# core.net
KiCad netlist of a schematic drawn in EAGLE
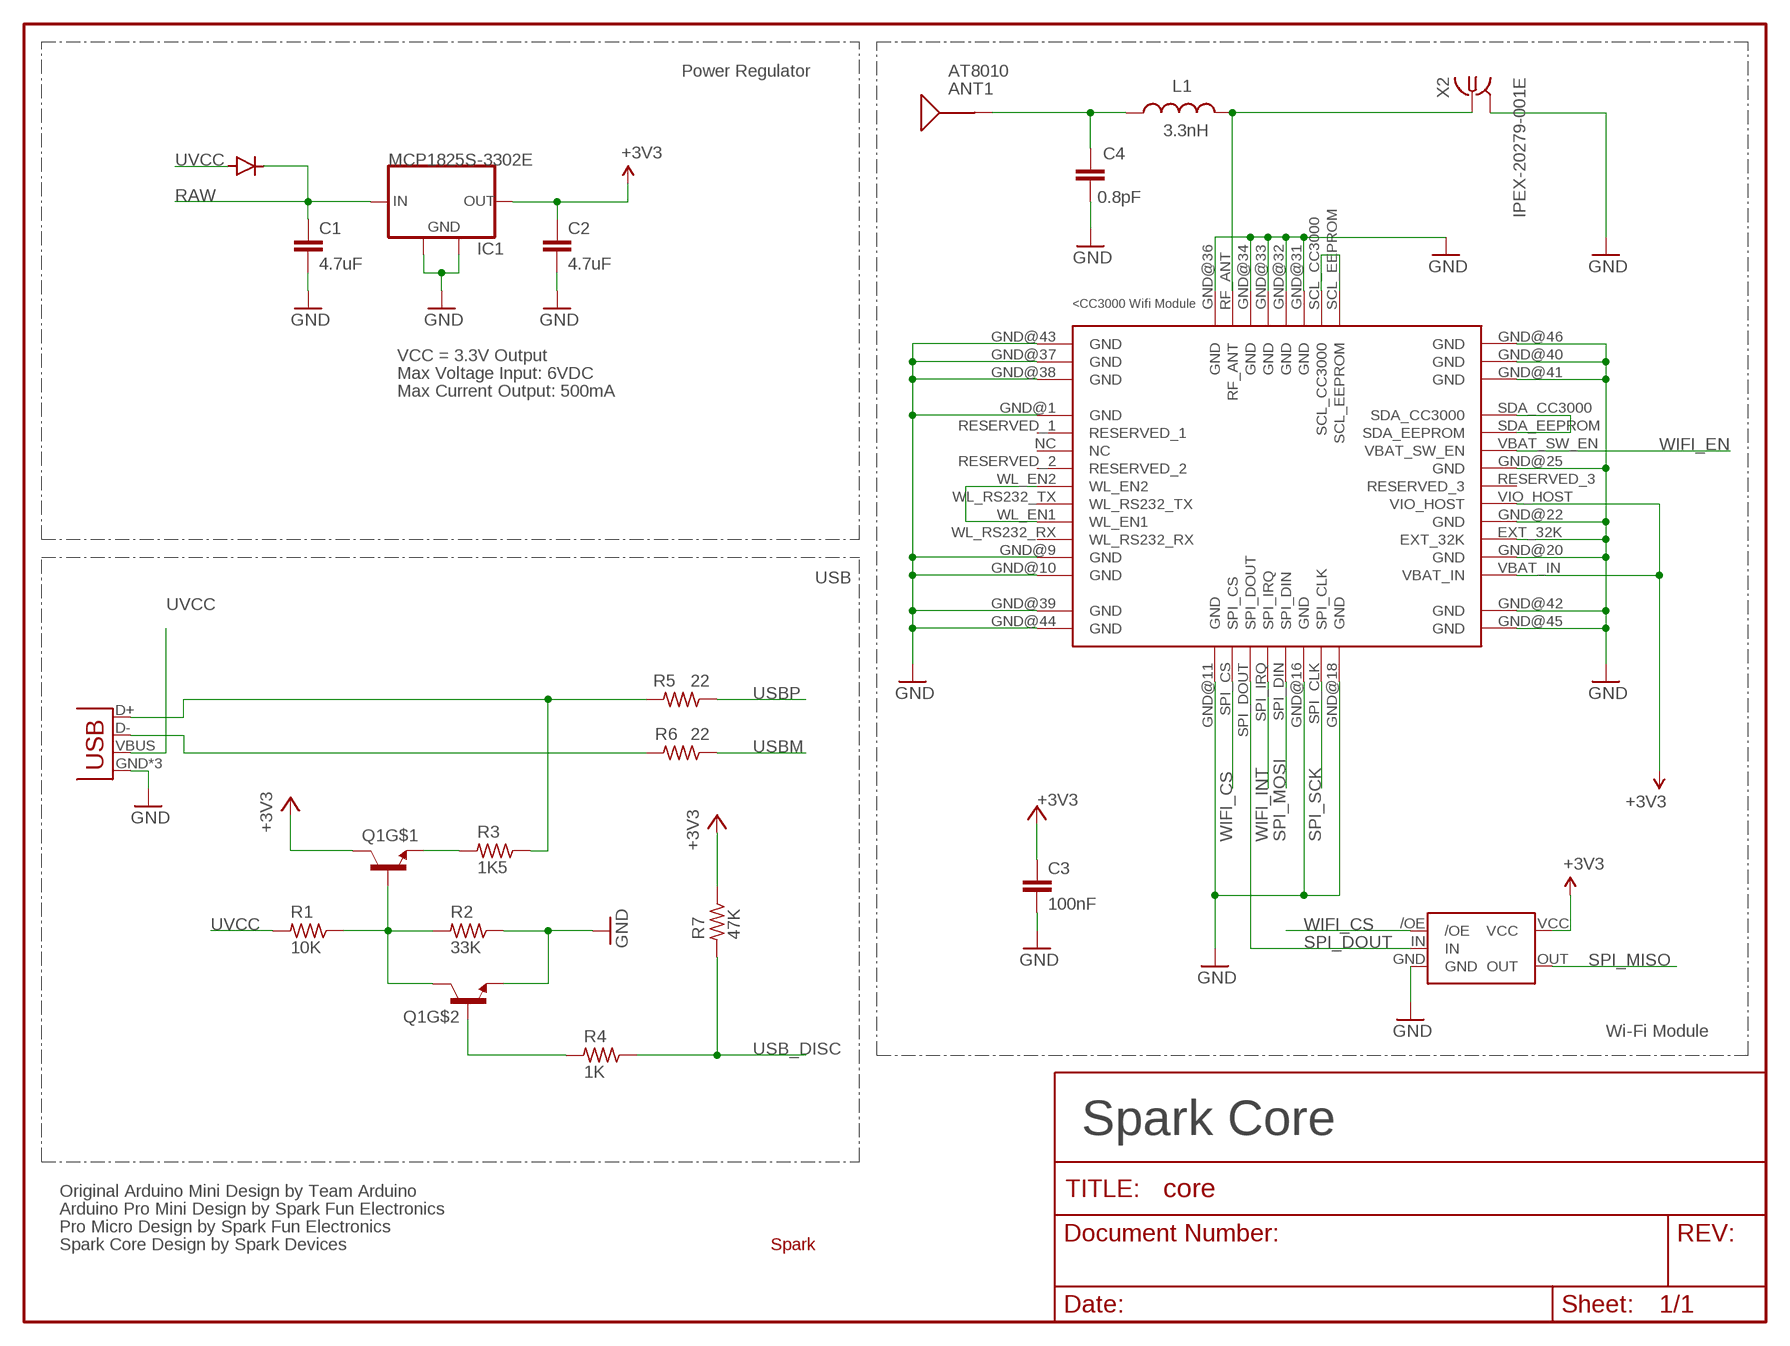
[diagram p0: schematic, sheet 1, part 1 of 2]
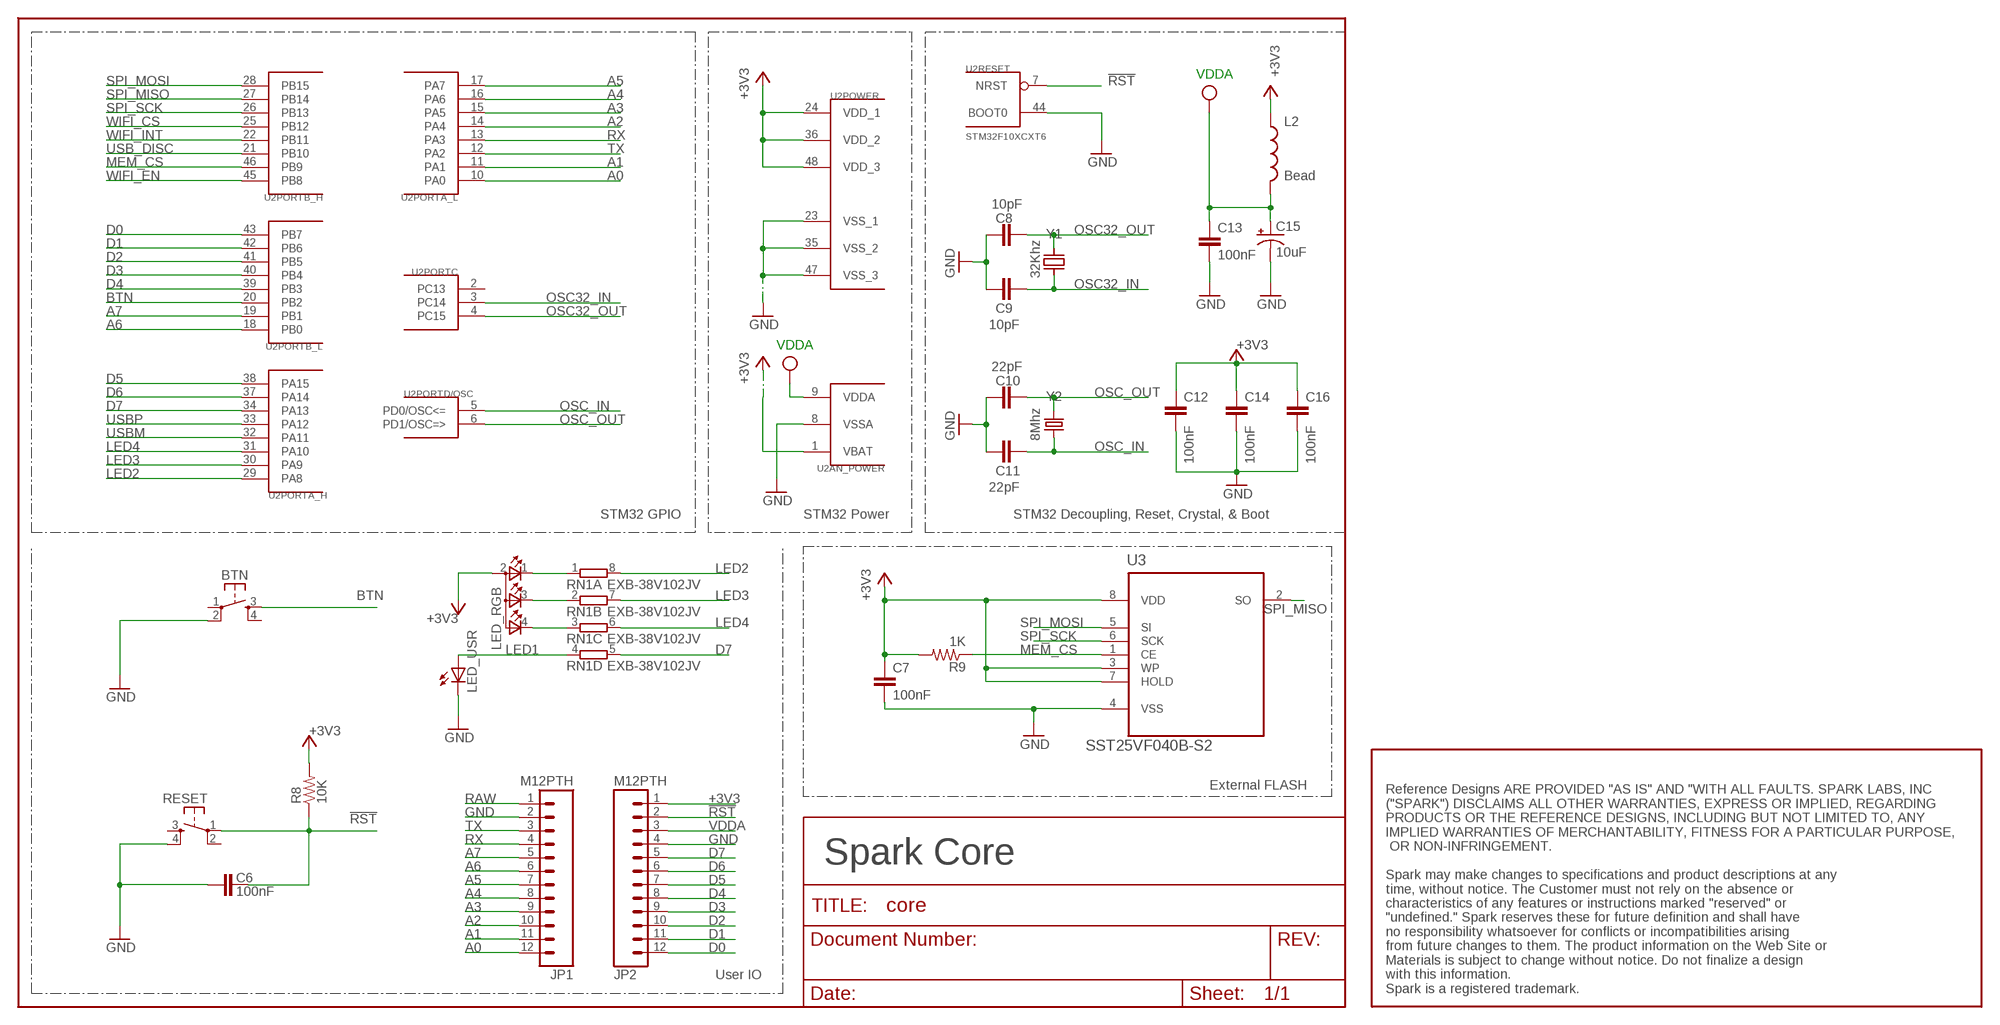
[diagram p1: schematic, sheet 1, part 2 of 2]

(export (version "E")
  (design (tool "Eeschema 10.0.6"))
  (components
    (comp (ref "ANT1")
      (value "AT8010")
      (footprint "eagle-import:AT8010")
      (libsource (lib "eagle-import") (part "AT8010"))
    )
    (comp (ref "BTN")
      (value "KMR211GLFS")
      (footprint "eagle-import:TACTILE_SWITCH_SMD")
      (libsource (lib "eagle-import") (part "TAC_SWITCHSMD"))
    )
    (comp (ref "C1")
      (value "4.7uF")
      (footprint "eagle-import:C0603")
      (libsource (lib "eagle-import") (part "C-EUC0603"))
    )
    (comp (ref "C2")
      (value "4.7uF")
      (footprint "eagle-import:C0603")
      (libsource (lib "eagle-import") (part "C-EUC0603"))
    )
    (comp (ref "C3")
      (value "100nF")
      (footprint "eagle-import:C0603")
      (libsource (lib "eagle-import") (part "C-EUC0603"))
    )
    (comp (ref "C4")
      (value "0.8pF")
      (footprint "eagle-import:C0603")
      (libsource (lib "eagle-import") (part "C-EUC0603"))
    )
    (comp (ref "C6")
      (value "100nF")
      (footprint "eagle-import:C0603")
      (libsource (lib "eagle-import") (part "C-EUC0603"))
    )
    (comp (ref "C7")
      (value "100nF")
      (footprint "eagle-import:C0603")
      (libsource (lib "eagle-import") (part "C-EUC0603"))
    )
    (comp (ref "C8")
      (value "10pF")
      (footprint "eagle-import:C0603")
      (libsource (lib "eagle-import") (part "C-EUC0603"))
    )
    (comp (ref "C9")
      (value "10pF")
      (footprint "eagle-import:C0603")
      (libsource (lib "eagle-import") (part "C-EUC0603"))
    )
    (comp (ref "C10")
      (value "22pF")
      (footprint "eagle-import:C0603")
      (libsource (lib "eagle-import") (part "C-EUC0603"))
    )
    (comp (ref "C11")
      (value "22pF")
      (footprint "eagle-import:C0603")
      (libsource (lib "eagle-import") (part "C-EUC0603"))
    )
    (comp (ref "C12")
      (value "100nF")
      (footprint "eagle-import:C0603")
      (libsource (lib "eagle-import") (part "C-EUC0603"))
    )
    (comp (ref "C13")
      (value "100nF")
      (footprint "eagle-import:C0603")
      (libsource (lib "eagle-import") (part "C-EUC0603"))
    )
    (comp (ref "C14")
      (value "100nF")
      (footprint "eagle-import:C0603")
      (libsource (lib "eagle-import") (part "C-EUC0603"))
    )
    (comp (ref "C15")
      (value "10uF")
      (footprint "eagle-import:EIA3216")
      (libsource (lib "eagle-import") (part "TANT-CAP1206"))
    )
    (comp (ref "C16")
      (value "100nF")
      (footprint "eagle-import:C0603")
      (libsource (lib "eagle-import") (part "C-EUC0603"))
    )
    (comp (ref "D1")
      (value "DIODE")
      (footprint "eagle-import:DIODE-DO-220AA(SMP)")
      (libsource (lib "eagle-import") (part "DIODE"))
    )
    (comp (ref "IC1")
      (value "MCP1825S-3302E")
      (footprint "eagle-import:SOT223")
      (libsource (lib "eagle-import") (part "MCP1825S-SOT223"))
    )
    (comp (ref "JP1")
      (value "M12PTH")
      (footprint "eagle-import:1X12-SMALL-PADS")
      (libsource (lib "eagle-import") (part "M12PTH"))
    )
    (comp (ref "JP2")
      (value "M12PTH")
      (footprint "eagle-import:1X12-SMALL-PADS")
      (libsource (lib "eagle-import") (part "M12PTH"))
    )
    (comp (ref "L1")
      (value "3.3nH")
      (footprint "eagle-import:0603")
      (libsource (lib "eagle-import") (part "INDUCTOR0603"))
    )
    (comp (ref "L2")
      (value "Bead")
      (footprint "eagle-import:0603")
      (libsource (lib "eagle-import") (part "INDUCTOR0603"))
    )
    (comp (ref "LED_RGB")
      (value "TOPLED-3PLCC")
      (footprint "eagle-import:P-LCC-4-3")
      (libsource (lib "eagle-import") (part "TOPLED-3PLCC"))
    )
    (comp (ref "LED_USR")
      (value "LED0603")
      (footprint "eagle-import:LED-0603")
      (libsource (lib "eagle-import") (part "LED0603"))
    )
    (comp (ref "Q1")
      (value "MMDT3904")
      (footprint "eagle-import:SOT363")
      (libsource (lib "eagle-import") (part "MMDT3904"))
    )
    (comp (ref "R1")
      (value "10K")
      (footprint "eagle-import:R0603")
      (libsource (lib "eagle-import") (part "R-US_R0603"))
    )
    (comp (ref "R2")
      (value "33K")
      (footprint "eagle-import:R0603")
      (libsource (lib "eagle-import") (part "R-US_R0603"))
    )
    (comp (ref "R3")
      (value "1K5")
      (footprint "eagle-import:R0603")
      (libsource (lib "eagle-import") (part "R-US_R0603"))
    )
    (comp (ref "R4")
      (value "1K")
      (footprint "eagle-import:R0603")
      (libsource (lib "eagle-import") (part "R-US_R0603"))
    )
    (comp (ref "R5")
      (value "22")
      (footprint "eagle-import:R0603")
      (libsource (lib "eagle-import") (part "R-US_R0603"))
    )
    (comp (ref "R6")
      (value "22")
      (footprint "eagle-import:R0603")
      (libsource (lib "eagle-import") (part "R-US_R0603"))
    )
    (comp (ref "R7")
      (value "47K")
      (footprint "eagle-import:R0603")
      (libsource (lib "eagle-import") (part "R-US_R0603"))
    )
    (comp (ref "R8")
      (value "10K")
      (footprint "eagle-import:R0603")
      (libsource (lib "eagle-import") (part "R-US_R0603"))
    )
    (comp (ref "R9")
      (value "1K")
      (footprint "eagle-import:R0603")
      (libsource (lib "eagle-import") (part "R-US_R0603"))
    )
    (comp (ref "RESET")
      (value "KMR211GLFS")
      (footprint "eagle-import:TACTILE_SWITCH_SMD")
      (libsource (lib "eagle-import") (part "TAC_SWITCHSMD"))
    )
    (comp (ref "RN1")
      (value "EXB-38V102JV")
      (footprint "eagle-import:EXB38V")
      (libsource (lib "eagle-import") (part "4R-NEXB38V"))
    )
    (comp (ref "U$1")
      (value "SPARK_LOGO2")
      (footprint "eagle-import:SPARK_LOGO2")
      (libsource (lib "eagle-import") (part "SPARK_LOGO2"))
    )
    (comp (ref "U1")
      (value "CC3000")
      (footprint "eagle-import:CC3000")
      (libsource (lib "eagle-import") (part "CC3000"))
    )
    (comp (ref "U2")
      (value "STM32F10XCXT6")
      (footprint "eagle-import:TQFP48")
      (libsource (lib "eagle-import") (part "STM32F10XCXT6"))
    )
    (comp (ref "U3")
      (value "SST25VF040B-S2")
      (footprint "eagle-import:SOIC127P790X216-8N")
      (libsource (lib "eagle-import") (part "SST25VF040B-S2"))
    )
    (comp (ref "U4")
      (value "NL17SZ125SOT553")
      (footprint "eagle-import:SOT-553")
      (libsource (lib "eagle-import") (part "NL17SZ125SOT553"))
    )
    (comp (ref "X1")
      (value "USB-MICROB")
      (footprint "eagle-import:USB-MICROB-SLOT-HOLE")
      (libsource (lib "eagle-import") (part "USBUSB-MICROB-SLOT-HOLE"))
    )
    (comp (ref "X2")
      (value "IPEX-20279-001E")
      (footprint "eagle-import:IPEX-20279-001E")
      (libsource (lib "eagle-import") (part "IPEX-20279-001E"))
    )
    (comp (ref "Y1")
      (value "32Khz")
      (footprint "eagle-import:FC135")
      (libsource (lib "eagle-import") (part "Q_FC135"))
    )
    (comp (ref "Y2")
      (value "8Mhz")
      (footprint "eagle-import:CRYSTAL-SMD-5X3")
      (libsource (lib "eagle-import") (part "CRYSTAL5X3"))
    )
  )
  (nets
    (net (code "1") (name "+3V3") (class "Default")
      (node (ref "C12") (pin "1") (pinfunction "1_1") (pintype "passive"))
      (node (ref "C14") (pin "1") (pinfunction "1_1") (pintype "passive"))
      (node (ref "C16") (pin "1") (pinfunction "1_1") (pintype "passive"))
      (node (ref "C2") (pin "1") (pinfunction "1_1") (pintype "passive"))
      (node (ref "C3") (pin "1") (pinfunction "1_1") (pintype "passive"))
      (node (ref "C7") (pin "1") (pinfunction "1_1") (pintype "passive"))
      (node (ref "IC1") (pin "3") (pinfunction "OUT_3") (pintype "output"))
      (node (ref "JP2") (pin "1") (pinfunction "1_1") (pintype "passive"))
      (node (ref "L2") (pin "1") (pinfunction "1_1") (pintype "passive"))
      (node (ref "LED_RGB") (pin "2") (pinfunction "A2_2") (pintype "passive"))
      (node (ref "Q1") (pin "3") (pinfunction "C_3") (pintype "passive"))
      (node (ref "R7") (pin "1") (pinfunction "1_1") (pintype "passive"))
      (node (ref "R8") (pin "2") (pinfunction "2_2") (pintype "passive"))
      (node (ref "R9") (pin "2") (pinfunction "2_2") (pintype "passive"))
      (node (ref "U1") (pin "VBAT_IN") (pinfunction "VBAT_IN_VBAT_IN") (pintype "power_in"))
      (node (ref "U1") (pin "VIO_HOST") (pinfunction "VIO_HOST_VIO_HOST") (pintype "power_in"))
      (node (ref "U2") (pin "1") (pinfunction "VBAT_1") (pintype "power_in"))
      (node (ref "U2") (pin "24") (pinfunction "VDD_1_24") (pintype "power_in"))
      (node (ref "U2") (pin "36") (pinfunction "VDD_2_36") (pintype "power_in"))
      (node (ref "U2") (pin "48") (pinfunction "VDD_3_48") (pintype "power_in"))
      (node (ref "U3") (pin "3") (pinfunction "WP_3") (pintype "input"))
      (node (ref "U3") (pin "7") (pinfunction "HOLD_7") (pintype "input"))
      (node (ref "U3") (pin "8") (pinfunction "VDD_8") (pintype "power_in"))
      (node (ref "U4") (pin "VCC") (pinfunction "VCC_VCC") (pintype "bidirectional"))
    )
    (net (code "2") (name "/A0") (class "Default")
      (node (ref "JP1") (pin "12") (pinfunction "12_12") (pintype "passive"))
      (node (ref "U2") (pin "10") (pinfunction "PA0_10") (pintype "bidirectional"))
    )
    (net (code "3") (name "/A1") (class "Default")
      (node (ref "JP1") (pin "11") (pinfunction "11_11") (pintype "passive"))
      (node (ref "U2") (pin "11") (pinfunction "PA1_11") (pintype "bidirectional"))
    )
    (net (code "4") (name "/A2") (class "Default")
      (node (ref "JP1") (pin "10") (pinfunction "10_10") (pintype "passive"))
      (node (ref "U2") (pin "14") (pinfunction "PA4_14") (pintype "bidirectional"))
    )
    (net (code "5") (name "/A3") (class "Default")
      (node (ref "JP1") (pin "9") (pinfunction "9_9") (pintype "passive"))
      (node (ref "U2") (pin "15") (pinfunction "PA5_15") (pintype "bidirectional"))
    )
    (net (code "6") (name "/A4") (class "Default")
      (node (ref "JP1") (pin "8") (pinfunction "8_8") (pintype "passive"))
      (node (ref "U2") (pin "16") (pinfunction "PA6_16") (pintype "bidirectional"))
    )
    (net (code "7") (name "/A5") (class "Default")
      (node (ref "JP1") (pin "7") (pinfunction "7_7") (pintype "passive"))
      (node (ref "U2") (pin "17") (pinfunction "PA7_17") (pintype "bidirectional"))
    )
    (net (code "8") (name "/A6") (class "Default")
      (node (ref "JP1") (pin "6") (pinfunction "6_6") (pintype "passive"))
      (node (ref "U2") (pin "18") (pinfunction "PB0_18") (pintype "bidirectional"))
    )
    (net (code "9") (name "/A7") (class "Default")
      (node (ref "JP1") (pin "5") (pinfunction "5_5") (pintype "passive"))
      (node (ref "U2") (pin "19") (pinfunction "PB1_19") (pintype "bidirectional"))
    )
    (net (code "10") (name "/BTN") (class "Default")
      (node (ref "BTN") (pin "3") (pinfunction "3_3") (pintype "passive"))
      (node (ref "U2") (pin "20") (pinfunction "PB2_20") (pintype "bidirectional"))
    )
    (net (code "11") (name "/D0") (class "Default")
      (node (ref "JP2") (pin "12") (pinfunction "12_12") (pintype "passive"))
      (node (ref "U2") (pin "43") (pinfunction "PB7_43") (pintype "bidirectional"))
    )
    (net (code "12") (name "/D1") (class "Default")
      (node (ref "JP2") (pin "11") (pinfunction "11_11") (pintype "passive"))
      (node (ref "U2") (pin "42") (pinfunction "PB6_42") (pintype "bidirectional"))
    )
    (net (code "13") (name "/D2") (class "Default")
      (node (ref "JP2") (pin "10") (pinfunction "10_10") (pintype "passive"))
      (node (ref "U2") (pin "41") (pinfunction "PB5_41") (pintype "bidirectional"))
    )
    (net (code "14") (name "/D3") (class "Default")
      (node (ref "JP2") (pin "9") (pinfunction "9_9") (pintype "passive"))
      (node (ref "U2") (pin "40") (pinfunction "PB4_40") (pintype "bidirectional"))
    )
    (net (code "15") (name "/D4") (class "Default")
      (node (ref "JP2") (pin "8") (pinfunction "8_8") (pintype "passive"))
      (node (ref "U2") (pin "39") (pinfunction "PB3_39") (pintype "bidirectional"))
    )
    (net (code "16") (name "/D5") (class "Default")
      (node (ref "JP2") (pin "7") (pinfunction "7_7") (pintype "passive"))
      (node (ref "U2") (pin "38") (pinfunction "PA15_38") (pintype "bidirectional"))
    )
    (net (code "17") (name "/D6") (class "Default")
      (node (ref "JP2") (pin "6") (pinfunction "6_6") (pintype "passive"))
      (node (ref "U2") (pin "37") (pinfunction "PA14_37") (pintype "bidirectional"))
    )
    (net (code "18") (name "/D7") (class "Default")
      (node (ref "JP2") (pin "5") (pinfunction "5_5") (pintype "passive"))
      (node (ref "RN1") (pin "5") (pinfunction "2_5") (pintype "passive"))
      (node (ref "U2") (pin "34") (pinfunction "PA13_34") (pintype "bidirectional"))
    )
    (net (code "19") (name "/LED1") (class "Default")
      (node (ref "LED_USR") (pin "A") (pinfunction "A_A") (pintype "passive"))
      (node (ref "RN1") (pin "4") (pinfunction "1_4") (pintype "passive"))
    )
    (net (code "20") (name "/LED2") (class "Default")
      (node (ref "RN1") (pin "8") (pinfunction "2_8") (pintype "passive"))
      (node (ref "U2") (pin "29") (pinfunction "PA8_29") (pintype "bidirectional"))
    )
    (net (code "21") (name "/LED3") (class "Default")
      (node (ref "RN1") (pin "7") (pinfunction "2_7") (pintype "passive"))
      (node (ref "U2") (pin "30") (pinfunction "PA9_30") (pintype "bidirectional"))
    )
    (net (code "22") (name "/LED4") (class "Default")
      (node (ref "RN1") (pin "6") (pinfunction "2_6") (pintype "passive"))
      (node (ref "U2") (pin "31") (pinfunction "PA10_31") (pintype "bidirectional"))
    )
    (net (code "23") (name "/MEM_CS") (class "Default")
      (node (ref "R9") (pin "1") (pinfunction "1_1") (pintype "passive"))
      (node (ref "U2") (pin "46") (pinfunction "PB9_46") (pintype "bidirectional"))
      (node (ref "U3") (pin "1") (pinfunction "CE_1") (pintype "input"))
    )
    (net (code "24") (name "/OSC32_IN") (class "Default")
      (node (ref "C9") (pin "1") (pinfunction "1_1") (pintype "passive"))
      (node (ref "U2") (pin "3") (pinfunction "PC14_3") (pintype "bidirectional"))
      (node (ref "Y1") (pin "X1") (pinfunction "1_X1") (pintype "passive"))
    )
    (net (code "25") (name "/OSC32_OUT") (class "Default")
      (node (ref "C8") (pin "1") (pinfunction "1_1") (pintype "passive"))
      (node (ref "U2") (pin "4") (pinfunction "PC15_4") (pintype "bidirectional"))
      (node (ref "Y1") (pin "X2") (pinfunction "2_X2") (pintype "passive"))
    )
    (net (code "26") (name "/OSC_IN") (class "Default")
      (node (ref "C11") (pin "1") (pinfunction "1_1") (pintype "passive"))
      (node (ref "U2") (pin "5") (pinfunction "PD0/OSC<=_5") (pintype "bidirectional"))
      (node (ref "Y2") (pin "1") (pinfunction "1_1") (pintype "passive"))
    )
    (net (code "27") (name "/OSC_OUT") (class "Default")
      (node (ref "C10") (pin "1") (pinfunction "1_1") (pintype "passive"))
      (node (ref "U2") (pin "6") (pinfunction "PD1/OSC=>_6") (pintype "bidirectional"))
      (node (ref "Y2") (pin "3") (pinfunction "2_3") (pintype "passive"))
    )
    (net (code "28") (name "/RAW") (class "Default")
      (node (ref "C1") (pin "1") (pinfunction "1_1") (pintype "passive"))
      (node (ref "D1") (pin "CATHODE") (pinfunction "CATHODE_CATHODE") (pintype "bidirectional"))
      (node (ref "IC1") (pin "1") (pinfunction "IN_1") (pintype "input"))
      (node (ref "JP1") (pin "1") (pinfunction "1_1") (pintype "passive"))
    )
    (net (code "29") (name "/RX") (class "Default")
      (node (ref "JP1") (pin "4") (pinfunction "4_4") (pintype "passive"))
      (node (ref "U2") (pin "13") (pinfunction "PA3_13") (pintype "bidirectional"))
    )
    (net (code "30") (name "/SPI_DOUT") (class "Default")
      (node (ref "U1") (pin "SPI_DOUT") (pinfunction "SPI_DOUT_SPI_DOUT") (pintype "output"))
      (node (ref "U4") (pin "IN") (pinfunction "IN_IN") (pintype "bidirectional"))
    )
    (net (code "31") (name "/SPI_MISO") (class "Default")
      (node (ref "U2") (pin "27") (pinfunction "PB14_27") (pintype "bidirectional"))
      (node (ref "U3") (pin "2") (pinfunction "SO_2") (pintype "output"))
      (node (ref "U4") (pin "OUT") (pinfunction "OUT_OUT") (pintype "bidirectional"))
    )
    (net (code "32") (name "/SPI_MOSI") (class "Default")
      (node (ref "U1") (pin "SPI_DIN") (pinfunction "SPI_DIN_SPI_DIN") (pintype "input"))
      (node (ref "U2") (pin "28") (pinfunction "PB15_28") (pintype "bidirectional"))
      (node (ref "U3") (pin "5") (pinfunction "SI_5") (pintype "input"))
    )
    (net (code "33") (name "/SPI_SCK") (class "Default")
      (node (ref "U1") (pin "SPI_CLK") (pinfunction "SPI_CLK_SPI_CLK") (pintype "input"))
      (node (ref "U2") (pin "26") (pinfunction "PB13_26") (pintype "bidirectional"))
      (node (ref "U3") (pin "6") (pinfunction "SCK_6") (pintype "input"))
    )
    (net (code "34") (name "/TX") (class "Default")
      (node (ref "JP1") (pin "3") (pinfunction "3_3") (pintype "passive"))
      (node (ref "U2") (pin "12") (pinfunction "PA2_12") (pintype "bidirectional"))
    )
    (net (code "35") (name "/USBM") (class "Default")
      (node (ref "R6") (pin "1") (pinfunction "1_1") (pintype "passive"))
      (node (ref "U2") (pin "32") (pinfunction "PA11_32") (pintype "bidirectional"))
    )
    (net (code "36") (name "/USBP") (class "Default")
      (node (ref "R5") (pin "1") (pinfunction "1_1") (pintype "passive"))
      (node (ref "U2") (pin "33") (pinfunction "PA12_33") (pintype "bidirectional"))
    )
    (net (code "37") (name "/USB_DISC") (class "Default")
      (node (ref "R4") (pin "1") (pinfunction "1_1") (pintype "passive"))
      (node (ref "R7") (pin "2") (pinfunction "2_2") (pintype "passive"))
      (node (ref "U2") (pin "21") (pinfunction "PB10_21") (pintype "bidirectional"))
    )
    (net (code "38") (name "/UVCC") (class "Default")
      (node (ref "D1") (pin "ANODE") (pinfunction "ANODE_ANODE") (pintype "bidirectional"))
      (node (ref "R1") (pin "2") (pinfunction "2_2") (pintype "passive"))
      (node (ref "X1") (pin "VBUS") (pinfunction "VBUS_VBUS") (pintype "bidirectional"))
    )
    (net (code "39") (name "/WIFI_CS") (class "Default")
      (node (ref "U1") (pin "SPI_CS") (pinfunction "SPI_CS_SPI_CS") (pintype "input"))
      (node (ref "U2") (pin "25") (pinfunction "PB12_25") (pintype "bidirectional"))
      (node (ref "U4") (pin "/OE") (pinfunction "/OE_/OE") (pintype "bidirectional"))
    )
    (net (code "40") (name "/WIFI_EN") (class "Default")
      (node (ref "U1") (pin "VBAT_SW_EN") (pinfunction "VBAT_SW_EN_VBAT_SW_EN") (pintype "input"))
      (node (ref "U2") (pin "45") (pinfunction "PB8_45") (pintype "bidirectional"))
    )
    (net (code "41") (name "/WIFI_INT") (class "Default")
      (node (ref "U1") (pin "SPI_IRQ") (pinfunction "SPI_IRQ_SPI_IRQ") (pintype "output"))
      (node (ref "U2") (pin "22") (pinfunction "PB11_22") (pintype "bidirectional"))
    )
    (net (code "42") (name "/~{RST}") (class "Default")
      (node (ref "C6") (pin "2") (pinfunction "2_2") (pintype "passive"))
      (node (ref "JP2") (pin "2") (pinfunction "2_2") (pintype "passive"))
      (node (ref "R8") (pin "1") (pinfunction "1_1") (pintype "passive"))
      (node (ref "RESET") (pin "1") (pinfunction "1_1") (pintype "passive"))
      (node (ref "U2") (pin "7") (pinfunction "NRST_7") (pintype "input"))
    )
    (net (code "43") (name "GND") (class "Default")
      (node (ref "BTN") (pin "2") (pinfunction "2_2") (pintype "passive"))
      (node (ref "C1") (pin "2") (pinfunction "2_2") (pintype "passive"))
      (node (ref "C10") (pin "2") (pinfunction "2_2") (pintype "passive"))
      (node (ref "C11") (pin "2") (pinfunction "2_2") (pintype "passive"))
      (node (ref "C12") (pin "2") (pinfunction "2_2") (pintype "passive"))
      (node (ref "C13") (pin "2") (pinfunction "2_2") (pintype "passive"))
      (node (ref "C14") (pin "2") (pinfunction "2_2") (pintype "passive"))
      (node (ref "C15") (pin "C") (pinfunction "-_C") (pintype "passive"))
      (node (ref "C16") (pin "2") (pinfunction "2_2") (pintype "passive"))
      (node (ref "C2") (pin "2") (pinfunction "2_2") (pintype "passive"))
      (node (ref "C3") (pin "2") (pinfunction "2_2") (pintype "passive"))
      (node (ref "C4") (pin "2") (pinfunction "2_2") (pintype "passive"))
      (node (ref "C6") (pin "1") (pinfunction "1_1") (pintype "passive"))
      (node (ref "C7") (pin "2") (pinfunction "2_2") (pintype "passive"))
      (node (ref "C8") (pin "2") (pinfunction "2_2") (pintype "passive"))
      (node (ref "C9") (pin "2") (pinfunction "2_2") (pintype "passive"))
      (node (ref "IC1") (pin "2") (pinfunction "GND_2") (pintype "power_in"))
      (node (ref "IC1") (pin "4") (pinfunction "GND_4") (pintype "power_in"))
      (node (ref "JP1") (pin "2") (pinfunction "2_2") (pintype "passive"))
      (node (ref "JP2") (pin "4") (pinfunction "4_4") (pintype "passive"))
      (node (ref "LED_USR") (pin "C") (pinfunction "C_C") (pintype "passive"))
      (node (ref "Q1") (pin "1") (pinfunction "E_1") (pintype "passive"))
      (node (ref "R2") (pin "1") (pinfunction "1_1") (pintype "passive"))
      (node (ref "RESET") (pin "4") (pinfunction "4_4") (pintype "passive"))
      (node (ref "U1") (pin "EXT_32K") (pinfunction "EXT_32K_EXT_32K") (pintype "bidirectional"))
      (node (ref "U1") (pin "GND@1") (pinfunction "GND_GND@1") (pintype "power_in"))
      (node (ref "U1") (pin "GND@10") (pinfunction "GND_GND@10") (pintype "power_in"))
      (node (ref "U1") (pin "GND@11") (pinfunction "GND_GND@11") (pintype "power_in"))
      (node (ref "U1") (pin "GND@16") (pinfunction "GND_GND@16") (pintype "power_in"))
      (node (ref "U1") (pin "GND@18") (pinfunction "GND_GND@18") (pintype "power_in"))
      (node (ref "U1") (pin "GND@20") (pinfunction "GND_GND@20") (pintype "power_in"))
      (node (ref "U1") (pin "GND@22") (pinfunction "GND_GND@22") (pintype "power_in"))
      (node (ref "U1") (pin "GND@25") (pinfunction "GND_GND@25") (pintype "power_in"))
      (node (ref "U1") (pin "GND@31") (pinfunction "GND_GND@31") (pintype "power_in"))
      (node (ref "U1") (pin "GND@32") (pinfunction "GND_GND@32") (pintype "power_in"))
      (node (ref "U1") (pin "GND@33") (pinfunction "GND_GND@33") (pintype "power_in"))
      (node (ref "U1") (pin "GND@34") (pinfunction "GND_GND@34") (pintype "power_in"))
      (node (ref "U1") (pin "GND@36") (pinfunction "GND_GND@36") (pintype "power_in"))
      (node (ref "U1") (pin "GND@37") (pinfunction "GND_GND@37") (pintype "power_in"))
      (node (ref "U1") (pin "GND@38") (pinfunction "GND_GND@38") (pintype "power_in"))
      (node (ref "U1") (pin "GND@39") (pinfunction "GND_GND@39") (pintype "power_in"))
      (node (ref "U1") (pin "GND@40") (pinfunction "GND_GND@40") (pintype "power_in"))
      (node (ref "U1") (pin "GND@41") (pinfunction "GND_GND@41") (pintype "power_in"))
      (node (ref "U1") (pin "GND@42") (pinfunction "GND_GND@42") (pintype "power_in"))
      (node (ref "U1") (pin "GND@43") (pinfunction "GND_GND@43") (pintype "power_in"))
      (node (ref "U1") (pin "GND@44") (pinfunction "GND_GND@44") (pintype "power_in"))
      (node (ref "U1") (pin "GND@45") (pinfunction "GND_GND@45") (pintype "power_in"))
      (node (ref "U1") (pin "GND@46") (pinfunction "GND_GND@46") (pintype "power_in"))
      (node (ref "U1") (pin "GND@9") (pinfunction "GND_GND@9") (pintype "power_in"))
      (node (ref "U2") (pin "23") (pinfunction "VSS_1_23") (pintype "power_in"))
      (node (ref "U2") (pin "35") (pinfunction "VSS_2_35") (pintype "power_in"))
      (node (ref "U2") (pin "44") (pinfunction "BOOT0_44") (pintype "input"))
      (node (ref "U2") (pin "47") (pinfunction "VSS_3_47") (pintype "power_in"))
      (node (ref "U2") (pin "8") (pinfunction "VSSA_8") (pintype "power_in"))
      (node (ref "U3") (pin "4") (pinfunction "VSS_4") (pintype "passive"))
      (node (ref "U4") (pin "GND") (pinfunction "GND_GND") (pintype "bidirectional"))
      (node (ref "X1") (pin "GND") (pinfunction "GND_GND") (pintype "bidirectional"))
      (node (ref "X1") (pin "MT1") (pinfunction "GND_MT1") (pintype "bidirectional"))
      (node (ref "X1") (pin "MT2") (pinfunction "GND_MT2") (pintype "bidirectional"))
      (node (ref "X2") (pin "2@1") (pinfunction "GND_2@1") (pintype "passive"))
      (node (ref "X2") (pin "2@2") (pinfunction "GND_2@2") (pintype "passive"))
    )
    (net (code "44") (name "Net-(ANT1-SIGNAL)") (class "Default")
      (node (ref "ANT1") (pin "SIG") (pinfunction "SIGNAL_SIG") (pintype "bidirectional"))
      (node (ref "C4") (pin "1") (pinfunction "1_1") (pintype "passive"))
      (node (ref "L1") (pin "1") (pinfunction "1_1") (pintype "passive"))
    )
    (net (code "45") (name "Net-(L1-Pad2)") (class "Default")
      (node (ref "L1") (pin "2") (pinfunction "2_2") (pintype "passive"))
      (node (ref "U1") (pin "RF_ANT") (pinfunction "RF_ANT_RF_ANT") (pintype "bidirectional"))
      (node (ref "X2") (pin "1") (pinfunction "1_1") (pintype "passive"))
    )
    (net (code "46") (name "Net-(LED_RGB-CBLUE)") (class "Default")
      (node (ref "LED_RGB") (pin "3") (pinfunction "CBLUE_3") (pintype "passive"))
      (node (ref "RN1") (pin "2") (pinfunction "1_2") (pintype "passive"))
    )
    (net (code "47") (name "Net-(LED_RGB-CGREEN)") (class "Default")
      (node (ref "LED_RGB") (pin "4") (pinfunction "CGREEN_4") (pintype "passive"))
      (node (ref "RN1") (pin "3") (pinfunction "1_3") (pintype "passive"))
    )
    (net (code "48") (name "Net-(LED_RGB-CRED)") (class "Default")
      (node (ref "LED_RGB") (pin "1") (pinfunction "CRED_1") (pintype "passive"))
      (node (ref "RN1") (pin "1") (pinfunction "1_1") (pintype "passive"))
    )
    (net (code "49") (name "Net-(Q1A-B)") (class "Default")
      (node (ref "Q1") (pin "5") (pinfunction "B_5") (pintype "passive"))
      (node (ref "Q1") (pin "6") (pinfunction "C_6") (pintype "passive"))
      (node (ref "R1") (pin "1") (pinfunction "1_1") (pintype "passive"))
      (node (ref "R2") (pin "2") (pinfunction "2_2") (pintype "passive"))
    )
    (net (code "50") (name "Net-(Q1A-E)") (class "Default")
      (node (ref "Q1") (pin "4") (pinfunction "E_4") (pintype "passive"))
      (node (ref "R3") (pin "2") (pinfunction "2_2") (pintype "passive"))
    )
    (net (code "51") (name "Net-(Q1B-B)") (class "Default")
      (node (ref "Q1") (pin "2") (pinfunction "B_2") (pintype "passive"))
      (node (ref "R4") (pin "2") (pinfunction "2_2") (pintype "passive"))
    )
    (net (code "52") (name "Net-(R3-Pad1)") (class "Default")
      (node (ref "R3") (pin "1") (pinfunction "1_1") (pintype "passive"))
      (node (ref "R5") (pin "2") (pinfunction "2_2") (pintype "passive"))
      (node (ref "X1") (pin "D+") (pinfunction "D+_D+") (pintype "bidirectional"))
    )
    (net (code "53") (name "Net-(R6-Pad2)") (class "Default")
      (node (ref "R6") (pin "2") (pinfunction "2_2") (pintype "passive"))
      (node (ref "X1") (pin "D-") (pinfunction "D-_D-") (pintype "bidirectional"))
    )
    (net (code "54") (name "Net-(U1-PadSCL_CC3000)") (class "Default")
      (node (ref "U1") (pin "SCL_CC3000") (pinfunction "SCL_CC3000_SCL_CC3000") (pintype "bidirectional"))
      (node (ref "U1") (pin "SCL_EEPROM") (pinfunction "SCL_EEPROM_SCL_EEPROM") (pintype "bidirectional"))
    )
    (net (code "55") (name "Net-(U1-PadSDA_CC3000)") (class "Default")
      (node (ref "U1") (pin "SDA_CC3000") (pinfunction "SDA_CC3000_SDA_CC3000") (pintype "bidirectional"))
      (node (ref "U1") (pin "SDA_EEPROM") (pinfunction "SDA_EEPROM_SDA_EEPROM") (pintype "bidirectional"))
    )
    (net (code "56") (name "Net-(U1-PadWL_EN1)") (class "Default")
      (node (ref "U1") (pin "WL_EN1") (pinfunction "WL_EN1_WL_EN1") (pintype "input"))
      (node (ref "U1") (pin "WL_EN2") (pinfunction "WL_EN2_WL_EN2") (pintype "input"))
    )
    (net (code "57") (name "VCC") (class "Default")
      (node (ref "C13") (pin "1") (pinfunction "1_1") (pintype "passive"))
      (node (ref "C15") (pin "A") (pinfunction "+_A") (pintype "passive"))
      (node (ref "JP2") (pin "3") (pinfunction "3_3") (pintype "passive"))
      (node (ref "L2") (pin "2") (pinfunction "2_2") (pintype "passive"))
      (node (ref "U2") (pin "9") (pinfunction "VDDA_9") (pintype "power_in"))
    )
    (net (code "58") (name "unconnected-(BTN-Pad1)") (class "Default")
      (node (ref "BTN") (pin "1") (pinfunction "1_1") (pintype "passive"))
    )
    (net (code "59") (name "unconnected-(BTN-Pad4)") (class "Default")
      (node (ref "BTN") (pin "4") (pinfunction "4_4") (pintype "passive"))
    )
    (net (code "60") (name "unconnected-(RESET-Pad2)") (class "Default")
      (node (ref "RESET") (pin "2") (pinfunction "2_2") (pintype "passive"))
    )
    (net (code "61") (name "unconnected-(RESET-Pad3)") (class "Default")
      (node (ref "RESET") (pin "3") (pinfunction "3_3") (pintype "passive"))
    )
    (net (code "62") (name "unconnected-(U1-PadNC)") (class "Default")
      (node (ref "U1") (pin "NC") (pinfunction "NC_NC") (pintype "no_connect"))
    )
    (net (code "63") (name "unconnected-(U1-PadRESERVED_1)") (class "Default")
      (node (ref "U1") (pin "RESERVED_1") (pinfunction "RESERVED_1_RESERVED_1") (pintype "bidirectional"))
    )
    (net (code "64") (name "unconnected-(U1-PadRESERVED_2)") (class "Default")
      (node (ref "U1") (pin "RESERVED_2") (pinfunction "RESERVED_2_RESERVED_2") (pintype "bidirectional"))
    )
    (net (code "65") (name "unconnected-(U1-PadRESERVED_3)") (class "Default")
      (node (ref "U1") (pin "RESERVED_3") (pinfunction "RESERVED_3_RESERVED_3") (pintype "bidirectional"))
    )
    (net (code "66") (name "unconnected-(U1-PadWL_RS232_RX)") (class "Default")
      (node (ref "U1") (pin "WL_RS232_RX") (pinfunction "WL_RS232_RX_WL_RS232_RX") (pintype "input"))
    )
    (net (code "67") (name "unconnected-(U1-PadWL_RS232_TX)") (class "Default")
      (node (ref "U1") (pin "WL_RS232_TX") (pinfunction "WL_RS232_TX_WL_RS232_TX") (pintype "output"))
    )
    (net (code "68") (name "unconnected-(U2F-PC13-Pad2)") (class "Default")
      (node (ref "U2") (pin "2") (pinfunction "PC13_2") (pintype "bidirectional"))
    )
  )
)
